# PCB.net
KiCad netlist of a schematic drawn in Altium Designer
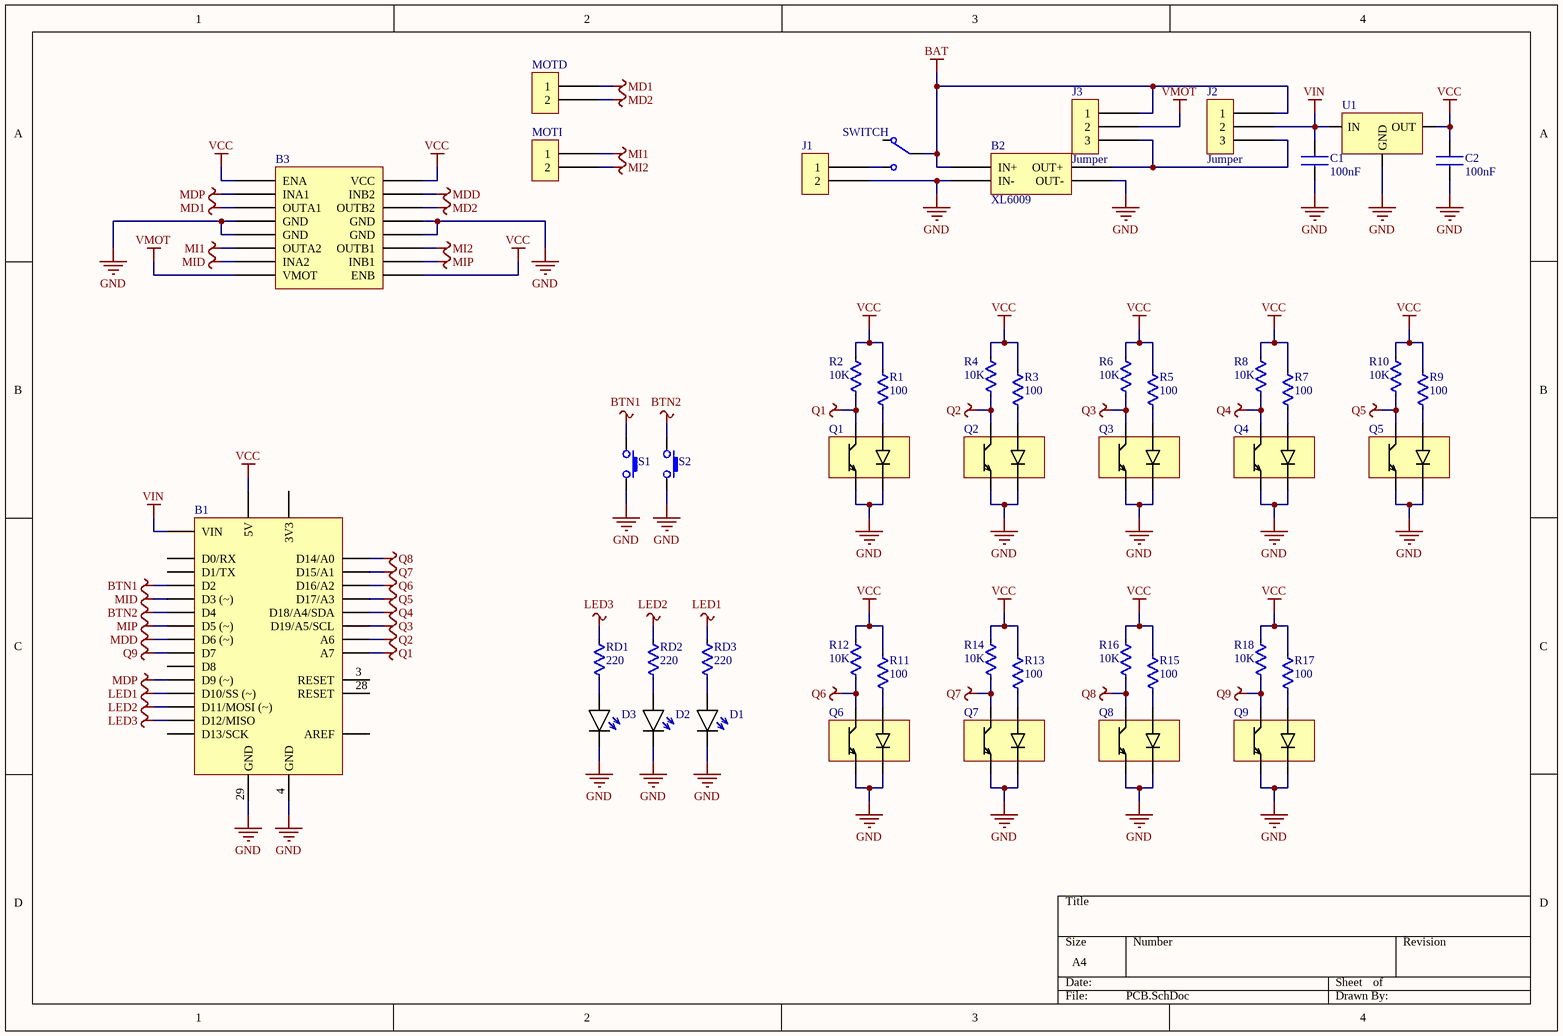
[diagram p0: PCB.SchDoc]

(export (version "E")
  (design (tool "Eeschema 10.0.6"))
  (components
    (comp (ref "B1")
      (value "ARDUINO NANO")
      (footprint "ARDUINO NANO")
      (fields (field (name "MANUFACTURER_PART_NUMBER") "Nano") (field (name "RS PART NUMBER") "6961667"))
      (libsource (lib "AltiumLibrary") (part "ARDUINO NANO"))
    )
    (comp (ref "B2")
      (value "XL6009")
      (footprint "XL6009 mdl")
      (libsource (lib "AltiumLibrary") (part "XL6009 Module"))
    )
    (comp (ref "B3") (value "L293D") (footprint "DIP16") (libsource (lib "AltiumLibrary") (part "L293")))
    (comp (ref "C1")
      (value "100nF")
      (footprint "CAP-CER")
      (fields (field (name "Comment") "CAP-CER"))
      (libsource (lib "AltiumLibrary") (part "CAP-CER"))
    )
    (comp (ref "C2")
      (value "100nF")
      (footprint "CAP-CER")
      (fields (field (name "Comment") "CAP-CER"))
      (libsource (lib "AltiumLibrary") (part "CAP-CER"))
    )
    (comp (ref "D1") (value "LED") (footprint "LED-3MM-GREEN") (libsource (lib "AltiumLibrary") (part "LED")))
    (comp (ref "D2")
      (value "LED")
      (footprint "LED-3MM-YELLOW")
      (libsource (lib "AltiumLibrary") (part "LED"))
    )
    (comp (ref "D3") (value "LED") (footprint "LED-3MM-RED") (libsource (lib "AltiumLibrary") (part "LED")))
    (comp (ref "J1")
      (value "Header 1x2")
      (footprint "HEADER 1x2")
      (libsource (lib "AltiumLibrary") (part "Header 1x2"))
    )
    (comp (ref "J2")
      (value "Jumper")
      (footprint "Header 1x3")
      (libsource (lib "AltiumLibrary") (part "Header 1x3"))
    )
    (comp (ref "J3")
      (value "Jumper")
      (footprint "Header 1x3")
      (libsource (lib "AltiumLibrary") (part "Header 1x3"))
    )
    (comp (ref "MOTD")
      (value "Header 1x2")
      (footprint "HEADER 1x2")
      (libsource (lib "AltiumLibrary") (part "Header 1x2"))
    )
    (comp (ref "MOTI")
      (value "Header 1x2")
      (footprint "HEADER 1x2")
      (libsource (lib "AltiumLibrary") (part "Header 1x2"))
    )
    (comp (ref "Q1")
      (value "QRE1113GR")
      (footprint "QRE1113GR")
      (fields (field (name "MF") "ON Semiconductor"))
      (libsource (lib "AltiumLibrary") (part "QRE1113GR"))
    )
    (comp (ref "Q2")
      (value "QRE1113GR")
      (footprint "QRE1113GR")
      (fields (field (name "MF") "ON Semiconductor"))
      (libsource (lib "AltiumLibrary") (part "QRE1113GR"))
    )
    (comp (ref "Q3")
      (value "QRE1113GR")
      (footprint "QRE1113GR")
      (fields (field (name "MF") "ON Semiconductor"))
      (libsource (lib "AltiumLibrary") (part "QRE1113GR"))
    )
    (comp (ref "Q4")
      (value "QRE1113GR")
      (footprint "QRE1113GR")
      (fields (field (name "MF") "ON Semiconductor"))
      (libsource (lib "AltiumLibrary") (part "QRE1113GR"))
    )
    (comp (ref "Q5")
      (value "QRE1113GR")
      (footprint "QRE1113GR")
      (fields (field (name "MF") "ON Semiconductor"))
      (libsource (lib "AltiumLibrary") (part "QRE1113GR"))
    )
    (comp (ref "Q6")
      (value "QRE1113GR")
      (footprint "QRE1113GR")
      (fields (field (name "MF") "ON Semiconductor"))
      (libsource (lib "AltiumLibrary") (part "QRE1113GR"))
    )
    (comp (ref "Q7")
      (value "QRE1113GR")
      (footprint "QRE1113GR")
      (fields (field (name "MF") "ON Semiconductor"))
      (libsource (lib "AltiumLibrary") (part "QRE1113GR"))
    )
    (comp (ref "Q8")
      (value "QRE1113GR")
      (footprint "QRE1113GR")
      (fields (field (name "MF") "ON Semiconductor"))
      (libsource (lib "AltiumLibrary") (part "QRE1113GR"))
    )
    (comp (ref "Q9")
      (value "QRE1113GR")
      (footprint "QRE1113GR")
      (fields (field (name "MF") "ON Semiconductor"))
      (libsource (lib "AltiumLibrary") (part "QRE1113GR"))
    )
    (comp (ref "R1")
      (value "100")
      (footprint "RES-Axial-400mil")
      (fields (field (name "Comment") "RES"))
      (libsource (lib "AltiumLibrary") (part "RES"))
    )
    (comp (ref "R2")
      (value "10K")
      (footprint "RES-Axial-400mil")
      (fields (field (name "Comment") "RES"))
      (libsource (lib "AltiumLibrary") (part "RES"))
    )
    (comp (ref "R3")
      (value "100")
      (footprint "RES-Axial-400mil")
      (fields (field (name "Comment") "RES"))
      (libsource (lib "AltiumLibrary") (part "RES"))
    )
    (comp (ref "R4")
      (value "10K")
      (footprint "RES-Axial-400mil")
      (fields (field (name "Comment") "RES"))
      (libsource (lib "AltiumLibrary") (part "RES"))
    )
    (comp (ref "R5")
      (value "100")
      (footprint "RES-Axial-400mil")
      (fields (field (name "Comment") "RES"))
      (libsource (lib "AltiumLibrary") (part "RES"))
    )
    (comp (ref "R6")
      (value "10K")
      (footprint "RES-Axial-400mil")
      (fields (field (name "Comment") "RES"))
      (libsource (lib "AltiumLibrary") (part "RES"))
    )
    (comp (ref "R7")
      (value "100")
      (footprint "RES-Axial-400mil")
      (fields (field (name "Comment") "RES"))
      (libsource (lib "AltiumLibrary") (part "RES"))
    )
    (comp (ref "R8")
      (value "10K")
      (footprint "RES-Axial-400mil")
      (fields (field (name "Comment") "RES"))
      (libsource (lib "AltiumLibrary") (part "RES"))
    )
    (comp (ref "R9")
      (value "100")
      (footprint "RES-Axial-400mil")
      (fields (field (name "Comment") "RES"))
      (libsource (lib "AltiumLibrary") (part "RES"))
    )
    (comp (ref "R10")
      (value "10K")
      (footprint "RES-Axial-400mil")
      (fields (field (name "Comment") "RES"))
      (libsource (lib "AltiumLibrary") (part "RES"))
    )
    (comp (ref "R11")
      (value "100")
      (footprint "RES-Axial-400mil")
      (fields (field (name "Comment") "RES"))
      (libsource (lib "AltiumLibrary") (part "RES"))
    )
    (comp (ref "R12")
      (value "10K")
      (footprint "RES-Axial-400mil")
      (fields (field (name "Comment") "RES"))
      (libsource (lib "AltiumLibrary") (part "RES"))
    )
    (comp (ref "R13")
      (value "100")
      (footprint "RES-Axial-400mil")
      (fields (field (name "Comment") "RES"))
      (libsource (lib "AltiumLibrary") (part "RES"))
    )
    (comp (ref "R14")
      (value "10K")
      (footprint "RES-Axial-400mil")
      (fields (field (name "Comment") "RES"))
      (libsource (lib "AltiumLibrary") (part "RES"))
    )
    (comp (ref "R15")
      (value "100")
      (footprint "RES-Axial-400mil")
      (fields (field (name "Comment") "RES"))
      (libsource (lib "AltiumLibrary") (part "RES"))
    )
    (comp (ref "R16")
      (value "10K")
      (footprint "RES-Axial-400mil")
      (fields (field (name "Comment") "RES"))
      (libsource (lib "AltiumLibrary") (part "RES"))
    )
    (comp (ref "R17")
      (value "100")
      (footprint "RES-Axial-400mil")
      (fields (field (name "Comment") "RES"))
      (libsource (lib "AltiumLibrary") (part "RES"))
    )
    (comp (ref "R18")
      (value "10K")
      (footprint "RES-Axial-400mil")
      (fields (field (name "Comment") "RES"))
      (libsource (lib "AltiumLibrary") (part "RES"))
    )
    (comp (ref "RD1")
      (value "220")
      (footprint "RES-RADIAL")
      (fields (field (name "Comment") "RES"))
      (libsource (lib "") (part "RES_1"))
    )
    (comp (ref "RD2")
      (value "220")
      (footprint "RES-RADIAL")
      (fields (field (name "Comment") "RES"))
      (libsource (lib "") (part "RES_1"))
    )
    (comp (ref "RD3")
      (value "220")
      (footprint "RES-RADIAL")
      (fields (field (name "Comment") "RES"))
      (libsource (lib "") (part "RES_1"))
    )
    (comp (ref "S1")
      (value "BUTTON_SMALL_4PIN")
      (footprint "TACT_SWITCH-SMALL-4PIN")
      (libsource (lib "AltiumLibrary") (part "BUTTON_SMALL_4PIN"))
    )
    (comp (ref "S2")
      (value "BUTTON_SMALL_4PIN")
      (footprint "TACT_SWITCH-SMALL-4PIN")
      (libsource (lib "AltiumLibrary") (part "BUTTON_SMALL_4PIN"))
    )
    (comp (ref "SWITCH")
      (value "SLIDE-SWITCH")
      (footprint "SWITCH")
      (libsource (lib "AltiumLibrary") (part "SLIDE-SWITCH"))
    )
    (comp (ref "U1")
      (value "LM7805")
      (footprint "TO-220-STRAIGHT")
      (libsource (lib "AltiumLibrary") (part "LM78XX"))
    )
  )
  (nets
    (net (code "1") (name "BAT") (class "Default")
      (node (ref "B2") (pin "0") (pinfunction "IN+_0") (pintype "passive"))
      (node (ref "J2") (pin "1") (pinfunction "1_1") (pintype "passive"))
      (node (ref "J3") (pin "1") (pinfunction "1_1") (pintype "passive"))
      (node (ref "SWITCH") (pin "2") (pintype "power_in"))
    )
    (net (code "2") (name "BTN1") (class "Default")
      (node (ref "B1") (pin "5") (pinfunction "D2_5") (pintype "passive"))
      (node (ref "S1") (pin "1") (pintype "passive"))
    )
    (net (code "3") (name "BTN2") (class "Default")
      (node (ref "B1") (pin "7") (pinfunction "D4_7") (pintype "passive"))
      (node (ref "S2") (pin "1") (pintype "passive"))
    )
    (net (code "4") (name "GND") (class "Default")
      (node (ref "B1") (pin "29") (pinfunction "GND_29") (pintype "passive"))
      (node (ref "B1") (pin "4") (pinfunction "GND_4") (pintype "passive"))
      (node (ref "B2") (pin "1") (pinfunction "IN-_1") (pintype "passive"))
      (node (ref "B2") (pin "2") (pinfunction "OUT-_2") (pintype "passive"))
      (node (ref "B3") (pin "12") (pinfunction "GND_12") (pintype "passive"))
      (node (ref "B3") (pin "13") (pinfunction "GND_13") (pintype "passive"))
      (node (ref "B3") (pin "4") (pinfunction "GND_4") (pintype "passive"))
      (node (ref "B3") (pin "5") (pinfunction "GND_5") (pintype "passive"))
      (node (ref "C1") (pin "1") (pintype "passive"))
      (node (ref "C2") (pin "1") (pintype "passive"))
      (node (ref "D1") (pin "K") (pintype "passive"))
      (node (ref "D2") (pin "K") (pintype "passive"))
      (node (ref "D3") (pin "K") (pintype "passive"))
      (node (ref "J1") (pin "2") (pinfunction "2_2") (pintype "passive"))
      (node (ref "Q1") (pin "E") (pinfunction "E_E") (pintype "passive"))
      (node (ref "Q1") (pin "K") (pinfunction "K_K") (pintype "passive"))
      (node (ref "Q2") (pin "E") (pinfunction "E_E") (pintype "passive"))
      (node (ref "Q2") (pin "K") (pinfunction "K_K") (pintype "passive"))
      (node (ref "Q3") (pin "E") (pinfunction "E_E") (pintype "passive"))
      (node (ref "Q3") (pin "K") (pinfunction "K_K") (pintype "passive"))
      (node (ref "Q4") (pin "E") (pinfunction "E_E") (pintype "passive"))
      (node (ref "Q4") (pin "K") (pinfunction "K_K") (pintype "passive"))
      (node (ref "Q5") (pin "E") (pinfunction "E_E") (pintype "passive"))
      (node (ref "Q5") (pin "K") (pinfunction "K_K") (pintype "passive"))
      (node (ref "Q6") (pin "E") (pinfunction "E_E") (pintype "passive"))
      (node (ref "Q6") (pin "K") (pinfunction "K_K") (pintype "passive"))
      (node (ref "Q7") (pin "E") (pinfunction "E_E") (pintype "passive"))
      (node (ref "Q7") (pin "K") (pinfunction "K_K") (pintype "passive"))
      (node (ref "Q8") (pin "E") (pinfunction "E_E") (pintype "passive"))
      (node (ref "Q8") (pin "K") (pinfunction "K_K") (pintype "passive"))
      (node (ref "Q9") (pin "E") (pinfunction "E_E") (pintype "passive"))
      (node (ref "Q9") (pin "K") (pinfunction "K_K") (pintype "passive"))
      (node (ref "S1") (pin "2") (pintype "passive"))
      (node (ref "S2") (pin "2") (pintype "passive"))
      (node (ref "U1") (pin "2") (pinfunction "GND_2") (pintype "power_in"))
    )
    (net (code "5") (name "LED1") (class "Default")
      (node (ref "B1") (pin "13") (pinfunction "D10/SS_(~)_13") (pintype "passive"))
      (node (ref "RD3") (pin "1") (pintype "passive"))
    )
    (net (code "6") (name "LED2") (class "Default")
      (node (ref "B1") (pin "14") (pinfunction "D11/MOSI_(~)_14") (pintype "passive"))
      (node (ref "RD2") (pin "1") (pintype "passive"))
    )
    (net (code "7") (name "LED3") (class "Default")
      (node (ref "B1") (pin "15") (pinfunction "D12/MISO_15") (pintype "passive"))
      (node (ref "RD1") (pin "1") (pintype "passive"))
    )
    (net (code "8") (name "MD1") (class "Default")
      (node (ref "B3") (pin "3") (pinfunction "OUTA1_3") (pintype "passive"))
      (node (ref "MOTD") (pin "1") (pinfunction "1_1") (pintype "passive"))
    )
    (net (code "9") (name "MD2") (class "Default")
      (node (ref "B3") (pin "14") (pinfunction "OUTB2_14") (pintype "passive"))
      (node (ref "MOTD") (pin "2") (pinfunction "2_2") (pintype "passive"))
    )
    (net (code "10") (name "MDD") (class "Default")
      (node (ref "B1") (pin "9") (pinfunction "D6_(~)_9") (pintype "passive"))
      (node (ref "B3") (pin "15") (pinfunction "INB2_15") (pintype "passive"))
    )
    (net (code "11") (name "MDP") (class "Default")
      (node (ref "B1") (pin "12") (pinfunction "D9_(~)_12") (pintype "passive"))
      (node (ref "B3") (pin "2") (pinfunction "INA1_2") (pintype "passive"))
    )
    (net (code "12") (name "MI1") (class "Default")
      (node (ref "B3") (pin "6") (pinfunction "OUTA2_6") (pintype "passive"))
      (node (ref "MOTI") (pin "1") (pinfunction "1_1") (pintype "passive"))
    )
    (net (code "13") (name "MI2") (class "Default")
      (node (ref "B3") (pin "11") (pinfunction "OUTB1_11") (pintype "passive"))
      (node (ref "MOTI") (pin "2") (pinfunction "2_2") (pintype "passive"))
    )
    (net (code "14") (name "MID") (class "Default")
      (node (ref "B1") (pin "6") (pinfunction "D3_(~)_6") (pintype "passive"))
      (node (ref "B3") (pin "7") (pinfunction "INA2_7") (pintype "passive"))
    )
    (net (code "15") (name "MIP") (class "Default")
      (node (ref "B1") (pin "8") (pinfunction "D5_(~)_8") (pintype "passive"))
      (node (ref "B3") (pin "10") (pinfunction "INB1_10") (pintype "passive"))
    )
    (net (code "16") (name "Net-(B2-OUT+)") (class "Default")
      (node (ref "B2") (pin "3") (pinfunction "OUT+_3") (pintype "passive"))
      (node (ref "J2") (pin "3") (pinfunction "3_3") (pintype "passive"))
      (node (ref "J3") (pin "3") (pinfunction "3_3") (pintype "passive"))
    )
    (net (code "17") (name "Net-(D1-PadA)") (class "Default")
      (node (ref "D1") (pin "A") (pintype "passive"))
      (node (ref "RD3") (pin "2") (pintype "passive"))
    )
    (net (code "18") (name "Net-(D2-PadA)") (class "Default")
      (node (ref "D2") (pin "A") (pintype "passive"))
      (node (ref "RD2") (pin "2") (pintype "passive"))
    )
    (net (code "19") (name "Net-(D3-PadA)") (class "Default")
      (node (ref "D3") (pin "A") (pintype "passive"))
      (node (ref "RD1") (pin "2") (pintype "passive"))
    )
    (net (code "20") (name "Net-(J1-Pad1)") (class "Default")
      (node (ref "J1") (pin "1") (pinfunction "1_1") (pintype "passive"))
      (node (ref "SWITCH") (pin "3") (pintype "power_in"))
    )
    (net (code "21") (name "Net-(Q1-PadA)") (class "Default")
      (node (ref "Q1") (pin "A") (pinfunction "A_A") (pintype "passive"))
      (node (ref "R1") (pin "1") (pintype "passive"))
    )
    (net (code "22") (name "Net-(Q2-PadA)") (class "Default")
      (node (ref "Q2") (pin "A") (pinfunction "A_A") (pintype "passive"))
      (node (ref "R3") (pin "1") (pintype "passive"))
    )
    (net (code "23") (name "Net-(Q3-PadA)") (class "Default")
      (node (ref "Q3") (pin "A") (pinfunction "A_A") (pintype "passive"))
      (node (ref "R5") (pin "1") (pintype "passive"))
    )
    (net (code "24") (name "Net-(Q4-PadA)") (class "Default")
      (node (ref "Q4") (pin "A") (pinfunction "A_A") (pintype "passive"))
      (node (ref "R7") (pin "1") (pintype "passive"))
    )
    (net (code "25") (name "Net-(Q5-PadA)") (class "Default")
      (node (ref "Q5") (pin "A") (pinfunction "A_A") (pintype "passive"))
      (node (ref "R9") (pin "1") (pintype "passive"))
    )
    (net (code "26") (name "Net-(Q6-PadA)") (class "Default")
      (node (ref "Q6") (pin "A") (pinfunction "A_A") (pintype "passive"))
      (node (ref "R11") (pin "1") (pintype "passive"))
    )
    (net (code "27") (name "Net-(Q7-PadA)") (class "Default")
      (node (ref "Q7") (pin "A") (pinfunction "A_A") (pintype "passive"))
      (node (ref "R13") (pin "1") (pintype "passive"))
    )
    (net (code "28") (name "Net-(Q8-PadA)") (class "Default")
      (node (ref "Q8") (pin "A") (pinfunction "A_A") (pintype "passive"))
      (node (ref "R15") (pin "1") (pintype "passive"))
    )
    (net (code "29") (name "Net-(Q9-PadA)") (class "Default")
      (node (ref "Q9") (pin "A") (pinfunction "A_A") (pintype "passive"))
      (node (ref "R17") (pin "1") (pintype "passive"))
    )
    (net (code "30") (name "Q1") (class "Default")
      (node (ref "B1") (pin "26") (pinfunction "A7_26") (pintype "passive"))
      (node (ref "Q1") (pin "C") (pinfunction "C_C") (pintype "passive"))
      (node (ref "R2") (pin "1") (pintype "passive"))
    )
    (net (code "31") (name "Q2") (class "Default")
      (node (ref "B1") (pin "25") (pinfunction "A6_25") (pintype "passive"))
      (node (ref "Q2") (pin "C") (pinfunction "C_C") (pintype "passive"))
      (node (ref "R4") (pin "1") (pintype "passive"))
    )
    (net (code "32") (name "Q3") (class "Default")
      (node (ref "B1") (pin "24") (pinfunction "D19/A5/SCL_24") (pintype "passive"))
      (node (ref "Q3") (pin "C") (pinfunction "C_C") (pintype "passive"))
      (node (ref "R6") (pin "1") (pintype "passive"))
    )
    (net (code "33") (name "Q4") (class "Default")
      (node (ref "B1") (pin "23") (pinfunction "D18/A4/SDA_23") (pintype "passive"))
      (node (ref "Q4") (pin "C") (pinfunction "C_C") (pintype "passive"))
      (node (ref "R8") (pin "1") (pintype "passive"))
    )
    (net (code "34") (name "Q5") (class "Default")
      (node (ref "B1") (pin "22") (pinfunction "D17/A3_22") (pintype "passive"))
      (node (ref "Q5") (pin "C") (pinfunction "C_C") (pintype "passive"))
      (node (ref "R10") (pin "1") (pintype "passive"))
    )
    (net (code "35") (name "Q6") (class "Default")
      (node (ref "B1") (pin "21") (pinfunction "D16/A2_21") (pintype "passive"))
      (node (ref "Q6") (pin "C") (pinfunction "C_C") (pintype "passive"))
      (node (ref "R12") (pin "1") (pintype "passive"))
    )
    (net (code "36") (name "Q7") (class "Default")
      (node (ref "B1") (pin "20") (pinfunction "D15/A1_20") (pintype "passive"))
      (node (ref "Q7") (pin "C") (pinfunction "C_C") (pintype "passive"))
      (node (ref "R14") (pin "1") (pintype "passive"))
    )
    (net (code "37") (name "Q8") (class "Default")
      (node (ref "B1") (pin "19") (pinfunction "D14/A0_19") (pintype "passive"))
      (node (ref "Q8") (pin "C") (pinfunction "C_C") (pintype "passive"))
      (node (ref "R16") (pin "1") (pintype "passive"))
    )
    (net (code "38") (name "Q9") (class "Default")
      (node (ref "B1") (pin "10") (pinfunction "D7_10") (pintype "passive"))
      (node (ref "Q9") (pin "C") (pinfunction "C_C") (pintype "passive"))
      (node (ref "R18") (pin "1") (pintype "passive"))
    )
    (net (code "39") (name "VCC") (class "Default")
      (node (ref "B1") (pin "27") (pinfunction "5V_27") (pintype "passive"))
      (node (ref "B3") (pin "1") (pinfunction "ENA_1") (pintype "passive"))
      (node (ref "B3") (pin "16") (pinfunction "VCC_16") (pintype "passive"))
      (node (ref "B3") (pin "9") (pinfunction "ENB_9") (pintype "passive"))
      (node (ref "C2") (pin "2") (pintype "passive"))
      (node (ref "R1") (pin "2") (pintype "passive"))
      (node (ref "R10") (pin "2") (pintype "passive"))
      (node (ref "R11") (pin "2") (pintype "passive"))
      (node (ref "R12") (pin "2") (pintype "passive"))
      (node (ref "R13") (pin "2") (pintype "passive"))
      (node (ref "R14") (pin "2") (pintype "passive"))
      (node (ref "R15") (pin "2") (pintype "passive"))
      (node (ref "R16") (pin "2") (pintype "passive"))
      (node (ref "R17") (pin "2") (pintype "passive"))
      (node (ref "R18") (pin "2") (pintype "passive"))
      (node (ref "R2") (pin "2") (pintype "passive"))
      (node (ref "R3") (pin "2") (pintype "passive"))
      (node (ref "R4") (pin "2") (pintype "passive"))
      (node (ref "R5") (pin "2") (pintype "passive"))
      (node (ref "R6") (pin "2") (pintype "passive"))
      (node (ref "R7") (pin "2") (pintype "passive"))
      (node (ref "R8") (pin "2") (pintype "passive"))
      (node (ref "R9") (pin "2") (pintype "passive"))
      (node (ref "U1") (pin "3") (pinfunction "OUT_3") (pintype "power_in"))
    )
    (net (code "40") (name "VIN") (class "Default")
      (node (ref "B1") (pin "30") (pinfunction "VIN_30") (pintype "passive"))
      (node (ref "C1") (pin "2") (pintype "passive"))
      (node (ref "J2") (pin "2") (pinfunction "2_2") (pintype "passive"))
      (node (ref "U1") (pin "1") (pinfunction "IN_1") (pintype "power_in"))
    )
    (net (code "41") (name "VMOT") (class "Default")
      (node (ref "B3") (pin "8") (pinfunction "VMOT_8") (pintype "passive"))
      (node (ref "J3") (pin "2") (pinfunction "2_2") (pintype "passive"))
    )
    (net (code "42") (name "unconnected-(B1-3V3-Pad17)") (class "Default")
      (node (ref "B1") (pin "17") (pinfunction "3V3_17") (pintype "passive"))
    )
    (net (code "43") (name "unconnected-(B1-AREF-Pad18)") (class "Default")
      (node (ref "B1") (pin "18") (pinfunction "AREF_18") (pintype "passive"))
    )
    (net (code "44") (name "unconnected-(B1-D0{slash}RX-Pad2)") (class "Default")
      (node (ref "B1") (pin "2") (pinfunction "D0/RX_2") (pintype "passive"))
    )
    (net (code "45") (name "unconnected-(B1-D1{slash}TX-Pad1)") (class "Default")
      (node (ref "B1") (pin "1") (pinfunction "D1/TX_1") (pintype "passive"))
    )
    (net (code "46") (name "unconnected-(B1-D8-Pad11)") (class "Default")
      (node (ref "B1") (pin "11") (pinfunction "D8_11") (pintype "passive"))
    )
    (net (code "47") (name "unconnected-(B1-D13{slash}SCK-Pad16)") (class "Default")
      (node (ref "B1") (pin "16") (pinfunction "D13/SCK_16") (pintype "passive"))
    )
    (net (code "48") (name "unconnected-(B1-RESET-Pad3)") (class "Default")
      (node (ref "B1") (pin "3") (pinfunction "RESET_3") (pintype "passive"))
    )
    (net (code "49") (name "unconnected-(B1-RESET-Pad28)") (class "Default")
      (node (ref "B1") (pin "28") (pinfunction "RESET_28") (pintype "passive"))
    )
    (net (code "50") (name "unconnected-(SWITCH-Pad1)") (class "Default")
      (node (ref "SWITCH") (pin "1") (pintype "power_in"))
    )
  )
)
